# MidPwm.net
KiCad netlist of a schematic drawn in Altium Designer
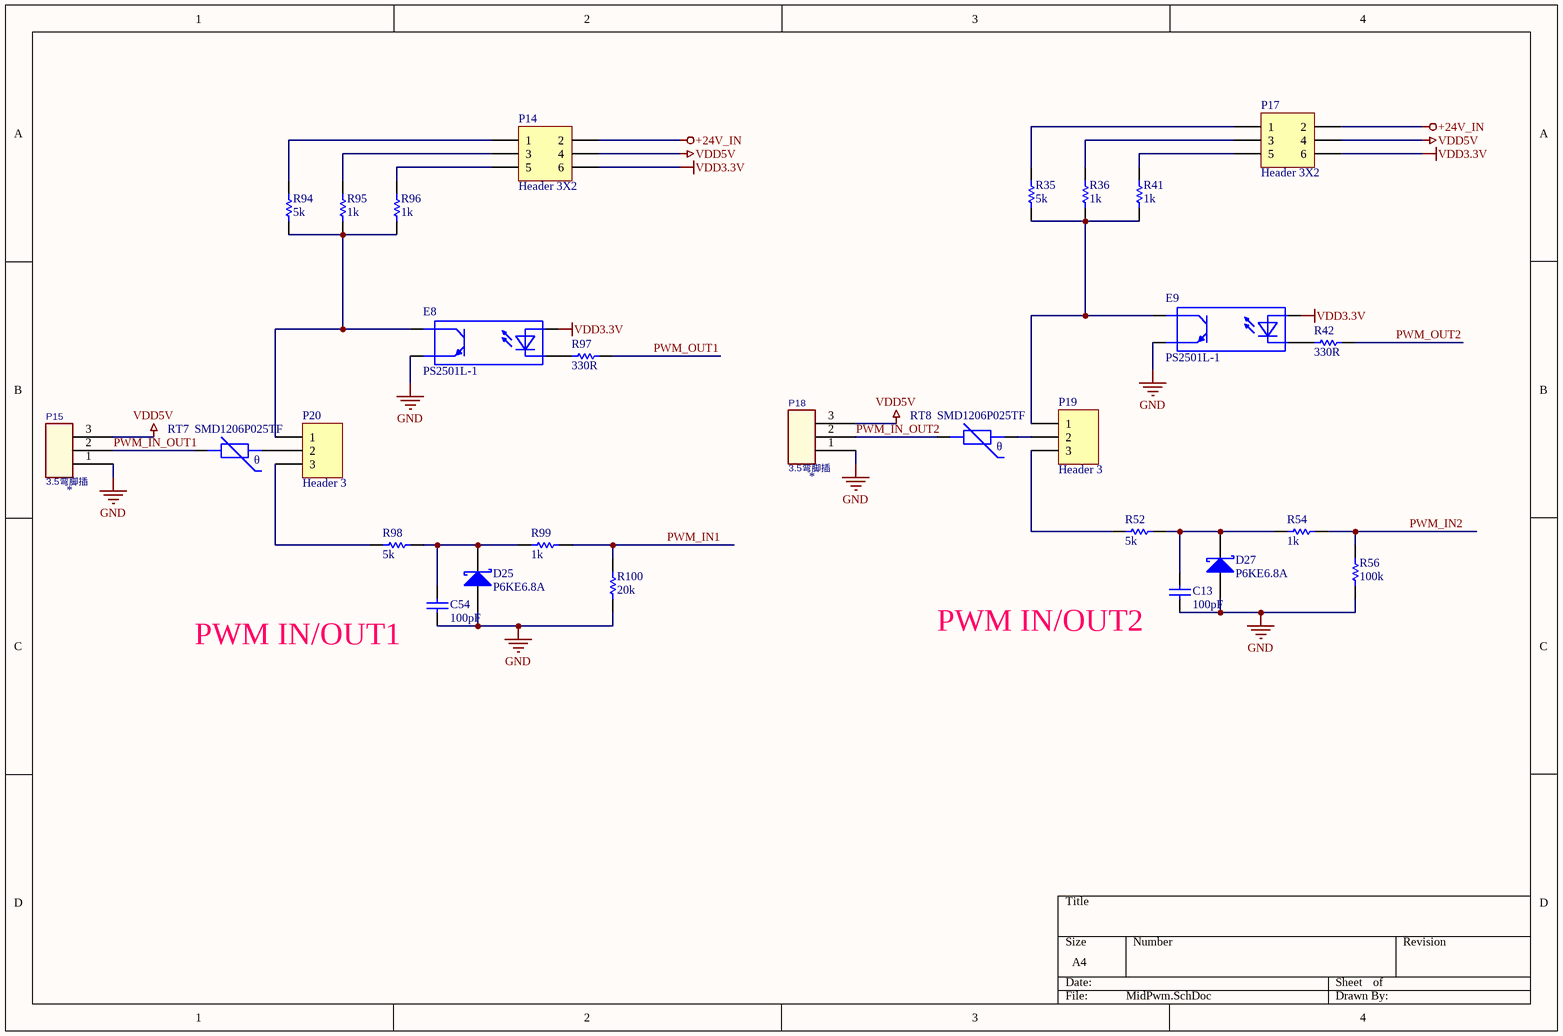
[diagram p0: MidPwm.SchDoc]

(export (version "E")
  (design (tool "Eeschema 10.0.6"))
  (components
    (comp (ref "C13")
      (value "100pF")
      (footprint "C0805")
      (description "Capacitor")
      (fields
        (field (name "MANUFACTURER") "Generic Components")
        (field (name "Comment") "Cap")
        (field (name "PUBLISHER") "Altium Hobart Technology Centre")
      )
      (libsource (lib "Miscellaneous Devices") (part "Cap"))
    )
    (comp (ref "C54")
      (value "100pF")
      (footprint "C0805")
      (description "Capacitor")
      (fields
        (field (name "MANUFACTURER") "Generic Components")
        (field (name "Comment") "Cap")
        (field (name "PUBLISHER") "Altium Hobart Technology Centre")
      )
      (libsource (lib "Miscellaneous Devices") (part "Cap"))
    )
    (comp (ref "D25")
      (value "P6KE6.8A")
      (footprint "SMB")
      (description "Schottky Diode")
      (fields (field (name "PUBLISHER") "Altium Limited"))
      (libsource (lib "Miscellaneous Devices") (part "D Schottky"))
    )
    (comp (ref "D27")
      (value "P6KE6.8A")
      (footprint "SMB")
      (description "Schottky Diode")
      (fields (field (name "PUBLISHER") "Altium Limited"))
      (libsource (lib "Miscellaneous Devices") (part "D Schottky"))
    )
    (comp (ref "E8") (value "PS2501L-1") (description "光耦") (libsource (lib "*") (part "OPTO1")))
    (comp (ref "E9") (value "PS2501L-1") (description "光耦") (libsource (lib "*") (part "OPTO1")))
    (comp (ref "P14")
      (value "Header 3X2")
      (footprint "HDR2X3")
      (description "Header, 3-Pin, Dual row")
      (fields (field (name "PUBLISHER") "Altium Limited"))
      (libsource (lib "Miscellaneous Connectors") (part "Header 3X2"))
    )
    (comp (ref "P15")
      (value "*")
      (footprint "3.5-P3")
      (fields (field (name "ALTIUM_UNNAMED_1") "3.5Íä½Å²å"))
      (libsource (lib "*") (part "CON3"))
    )
    (comp (ref "P17")
      (value "Header 3X2")
      (footprint "HDR2X3")
      (description "Header, 3-Pin, Dual row")
      (fields (field (name "PUBLISHER") "Altium Limited"))
      (libsource (lib "Miscellaneous Connectors") (part "Header 3X2"))
    )
    (comp (ref "P18")
      (value "*")
      (footprint "3.5-P3")
      (fields (field (name "ALTIUM_UNNAMED_1") "3.5Íä½Å²å"))
      (libsource (lib "*") (part "CON3"))
    )
    (comp (ref "P19")
      (value "Header 3")
      (footprint "HDR1X3")
      (description "Header, 3-Pin")
      (fields (field (name "PUBLISHER") "Altium Limited"))
      (libsource (lib "Miscellaneous Connectors") (part "Header 3"))
    )
    (comp (ref "P20")
      (value "Header 3")
      (footprint "HDR1X3")
      (description "Header, 3-Pin")
      (fields (field (name "PUBLISHER") "Altium Limited"))
      (libsource (lib "Miscellaneous Connectors") (part "Header 3"))
    )
    (comp (ref "R35")
      (value "5k")
      (footprint "0805")
      (description "Semiconductor Resistor")
      (fields (field (name "Comment") "Res Semi") (field (name "PUBLISHER") "Altium Limited"))
      (libsource (lib "Miscellaneous Devices") (part "Res Semi"))
    )
    (comp (ref "R36")
      (value "1k")
      (footprint "0805")
      (description "Semiconductor Resistor")
      (fields (field (name "Comment") "Res Semi") (field (name "PUBLISHER") "Altium Limited"))
      (libsource (lib "Miscellaneous Devices") (part "Res Semi"))
    )
    (comp (ref "R41")
      (value "1k")
      (footprint "0805")
      (description "Semiconductor Resistor")
      (fields (field (name "Comment") "Res Semi") (field (name "PUBLISHER") "Altium Limited"))
      (libsource (lib "Miscellaneous Devices") (part "Res Semi"))
    )
    (comp (ref "R42")
      (value "330R")
      (footprint "0805")
      (description "Semiconductor Resistor")
      (fields (field (name "Comment") "Res Semi") (field (name "PUBLISHER") "Altium Limited"))
      (libsource (lib "Miscellaneous Devices") (part "Res Semi"))
    )
    (comp (ref "R52")
      (value "5k")
      (footprint "0805")
      (description "Semiconductor Resistor")
      (fields (field (name "Comment") "Res Semi") (field (name "PUBLISHER") "Altium Limited"))
      (libsource (lib "Miscellaneous Devices") (part "Res Semi"))
    )
    (comp (ref "R54")
      (value "1k")
      (footprint "0805")
      (description "Semiconductor Resistor")
      (fields (field (name "Comment") "Res Semi") (field (name "PUBLISHER") "Altium Limited"))
      (libsource (lib "Miscellaneous Devices") (part "Res Semi"))
    )
    (comp (ref "R56")
      (value "100k")
      (footprint "0805")
      (description "Semiconductor Resistor")
      (fields (field (name "Comment") "Res Semi") (field (name "PUBLISHER") "Altium Limited"))
      (libsource (lib "Miscellaneous Devices") (part "Res Semi"))
    )
    (comp (ref "R94")
      (value "5k")
      (footprint "0805")
      (description "Semiconductor Resistor")
      (fields (field (name "Comment") "Res Semi") (field (name "PUBLISHER") "Altium Limited"))
      (libsource (lib "Miscellaneous Devices") (part "Res Semi"))
    )
    (comp (ref "R95")
      (value "1k")
      (footprint "0805")
      (description "Semiconductor Resistor")
      (fields (field (name "Comment") "Res Semi") (field (name "PUBLISHER") "Altium Limited"))
      (libsource (lib "Miscellaneous Devices") (part "Res Semi"))
    )
    (comp (ref "R96")
      (value "1k")
      (footprint "0805")
      (description "Semiconductor Resistor")
      (fields (field (name "Comment") "Res Semi") (field (name "PUBLISHER") "Altium Limited"))
      (libsource (lib "Miscellaneous Devices") (part "Res Semi"))
    )
    (comp (ref "R97")
      (value "330R")
      (footprint "0805")
      (description "Semiconductor Resistor")
      (fields (field (name "Comment") "Res Semi") (field (name "PUBLISHER") "Altium Limited"))
      (libsource (lib "Miscellaneous Devices") (part "Res Semi"))
    )
    (comp (ref "R98")
      (value "5k")
      (footprint "0805")
      (description "Semiconductor Resistor")
      (fields (field (name "Comment") "Res Semi") (field (name "PUBLISHER") "Altium Limited"))
      (libsource (lib "Miscellaneous Devices") (part "Res Semi"))
    )
    (comp (ref "R99")
      (value "1k")
      (footprint "0805")
      (description "Semiconductor Resistor")
      (fields (field (name "Comment") "Res Semi") (field (name "PUBLISHER") "Altium Limited"))
      (libsource (lib "Miscellaneous Devices") (part "Res Semi"))
    )
    (comp (ref "R100")
      (value "20k")
      (footprint "0805")
      (description "Semiconductor Resistor")
      (fields (field (name "Comment") "Res Semi") (field (name "PUBLISHER") "Altium Limited"))
      (libsource (lib "Miscellaneous Devices") (part "Res Semi"))
    )
    (comp (ref "RT7")
      (value "SMD1206P025TF")
      (footprint "1206")
      (description "热敏电阻")
      (libsource (lib "*") (part "PTC"))
    )
    (comp (ref "RT8")
      (value "SMD1206P025TF")
      (footprint "1206")
      (description "热敏电阻")
      (libsource (lib "*") (part "PTC"))
    )
  )
  (nets
    (net (code "1") (name "+24V_IN") (class "Default")
      (node (ref "P14") (pin "2") (pinfunction "2_2") (pintype "passive"))
      (node (ref "P17") (pin "2") (pinfunction "2_2") (pintype "passive"))
    )
    (net (code "2") (name "/PWM_IN1") (class "Default")
      (node (ref "R100") (pin "1") (pinfunction "1_1") (pintype "passive"))
      (node (ref "R99") (pin "2") (pinfunction "2_2") (pintype "passive"))
    )
    (net (code "3") (name "/PWM_IN2") (class "Default")
      (node (ref "R54") (pin "2") (pinfunction "2_2") (pintype "passive"))
      (node (ref "R56") (pin "1") (pinfunction "1_1") (pintype "passive"))
    )
    (net (code "4") (name "/PWM_IN_OUT1") (class "Default")
      (node (ref "P15") (pin "2") (pinfunction "2_2") (pintype "passive"))
      (node (ref "RT7") (pin "1") (pintype "passive"))
    )
    (net (code "5") (name "/PWM_IN_OUT2") (class "Default")
      (node (ref "P18") (pin "2") (pinfunction "2_2") (pintype "passive"))
      (node (ref "RT8") (pin "1") (pintype "passive"))
    )
    (net (code "6") (name "/PWM_OUT1") (class "Default")
      (node (ref "R97") (pin "2") (pinfunction "2_2") (pintype "passive"))
    )
    (net (code "7") (name "/PWM_OUT2") (class "Default")
      (node (ref "R42") (pin "2") (pinfunction "2_2") (pintype "passive"))
    )
    (net (code "8") (name "GND") (class "Default")
      (node (ref "C13") (pin "2") (pinfunction "2_2") (pintype "passive"))
      (node (ref "C54") (pin "2") (pinfunction "2_2") (pintype "passive"))
      (node (ref "D25") (pin "1") (pinfunction "A_1") (pintype "passive"))
      (node (ref "D27") (pin "1") (pinfunction "A_1") (pintype "passive"))
      (node (ref "E8") (pin "3") (pintype "passive"))
      (node (ref "E9") (pin "3") (pintype "passive"))
      (node (ref "P15") (pin "1") (pinfunction "1_1") (pintype "passive"))
      (node (ref "P18") (pin "1") (pinfunction "1_1") (pintype "passive"))
      (node (ref "R100") (pin "2") (pinfunction "2_2") (pintype "passive"))
      (node (ref "R56") (pin "2") (pinfunction "2_2") (pintype "passive"))
    )
    (net (code "9") (name "Net-(D25-K)") (class "Default")
      (node (ref "C54") (pin "1") (pinfunction "1_1") (pintype "passive"))
      (node (ref "D25") (pin "2") (pinfunction "K_2") (pintype "passive"))
      (node (ref "R98") (pin "2") (pinfunction "2_2") (pintype "passive"))
      (node (ref "R99") (pin "1") (pinfunction "1_1") (pintype "passive"))
    )
    (net (code "10") (name "Net-(D27-K)") (class "Default")
      (node (ref "C13") (pin "1") (pinfunction "1_1") (pintype "passive"))
      (node (ref "D27") (pin "2") (pinfunction "K_2") (pintype "passive"))
      (node (ref "R52") (pin "2") (pinfunction "2_2") (pintype "passive"))
      (node (ref "R54") (pin "1") (pinfunction "1_1") (pintype "passive"))
    )
    (net (code "11") (name "Net-(E8-Pad2)") (class "Default")
      (node (ref "E8") (pin "2") (pintype "passive"))
      (node (ref "R97") (pin "1") (pinfunction "1_1") (pintype "passive"))
    )
    (net (code "12") (name "Net-(E8-Pad4)") (class "Default")
      (node (ref "E8") (pin "4") (pintype "passive"))
      (node (ref "P20") (pin "1") (pinfunction "1_1") (pintype "passive"))
      (node (ref "R94") (pin "2") (pinfunction "2_2") (pintype "passive"))
      (node (ref "R95") (pin "2") (pinfunction "2_2") (pintype "passive"))
      (node (ref "R96") (pin "2") (pinfunction "2_2") (pintype "passive"))
    )
    (net (code "13") (name "Net-(E9-Pad2)") (class "Default")
      (node (ref "E9") (pin "2") (pintype "passive"))
      (node (ref "R42") (pin "1") (pinfunction "1_1") (pintype "passive"))
    )
    (net (code "14") (name "Net-(E9-Pad4)") (class "Default")
      (node (ref "E9") (pin "4") (pintype "passive"))
      (node (ref "P19") (pin "1") (pinfunction "1_1") (pintype "passive"))
      (node (ref "R35") (pin "2") (pinfunction "2_2") (pintype "passive"))
      (node (ref "R36") (pin "2") (pinfunction "2_2") (pintype "passive"))
      (node (ref "R41") (pin "2") (pinfunction "2_2") (pintype "passive"))
    )
    (net (code "15") (name "Net-(P14-Pad1)") (class "Default")
      (node (ref "P14") (pin "1") (pinfunction "1_1") (pintype "passive"))
      (node (ref "R94") (pin "1") (pinfunction "1_1") (pintype "passive"))
    )
    (net (code "16") (name "Net-(P14-Pad3)") (class "Default")
      (node (ref "P14") (pin "3") (pinfunction "3_3") (pintype "passive"))
      (node (ref "R95") (pin "1") (pinfunction "1_1") (pintype "passive"))
    )
    (net (code "17") (name "Net-(P14-Pad5)") (class "Default")
      (node (ref "P14") (pin "5") (pinfunction "5_5") (pintype "passive"))
      (node (ref "R96") (pin "1") (pinfunction "1_1") (pintype "passive"))
    )
    (net (code "18") (name "Net-(P17-Pad1)") (class "Default")
      (node (ref "P17") (pin "1") (pinfunction "1_1") (pintype "passive"))
      (node (ref "R35") (pin "1") (pinfunction "1_1") (pintype "passive"))
    )
    (net (code "19") (name "Net-(P17-Pad3)") (class "Default")
      (node (ref "P17") (pin "3") (pinfunction "3_3") (pintype "passive"))
      (node (ref "R36") (pin "1") (pinfunction "1_1") (pintype "passive"))
    )
    (net (code "20") (name "Net-(P17-Pad5)") (class "Default")
      (node (ref "P17") (pin "5") (pinfunction "5_5") (pintype "passive"))
      (node (ref "R41") (pin "1") (pinfunction "1_1") (pintype "passive"))
    )
    (net (code "21") (name "Net-(P19-Pad2)") (class "Default")
      (node (ref "P19") (pin "2") (pinfunction "2_2") (pintype "passive"))
      (node (ref "RT8") (pin "2") (pintype "passive"))
    )
    (net (code "22") (name "Net-(P19-Pad3)") (class "Default")
      (node (ref "P19") (pin "3") (pinfunction "3_3") (pintype "passive"))
      (node (ref "R52") (pin "1") (pinfunction "1_1") (pintype "passive"))
    )
    (net (code "23") (name "Net-(P20-Pad2)") (class "Default")
      (node (ref "P20") (pin "2") (pinfunction "2_2") (pintype "passive"))
      (node (ref "RT7") (pin "2") (pintype "passive"))
    )
    (net (code "24") (name "Net-(P20-Pad3)") (class "Default")
      (node (ref "P20") (pin "3") (pinfunction "3_3") (pintype "passive"))
      (node (ref "R98") (pin "1") (pinfunction "1_1") (pintype "passive"))
    )
    (net (code "25") (name "VDD3.3V") (class "Default")
      (node (ref "E8") (pin "1") (pintype "passive"))
      (node (ref "E9") (pin "1") (pintype "passive"))
      (node (ref "P14") (pin "6") (pinfunction "6_6") (pintype "passive"))
      (node (ref "P17") (pin "6") (pinfunction "6_6") (pintype "passive"))
    )
    (net (code "26") (name "VDD5V") (class "Default")
      (node (ref "P14") (pin "4") (pinfunction "4_4") (pintype "passive"))
      (node (ref "P15") (pin "3") (pinfunction "3_3") (pintype "passive"))
      (node (ref "P17") (pin "4") (pinfunction "4_4") (pintype "passive"))
      (node (ref "P18") (pin "3") (pinfunction "3_3") (pintype "passive"))
    )
  )
)
